# Ejercicio3.net
KiCad netlist of a schematic drawn in Altium Designer
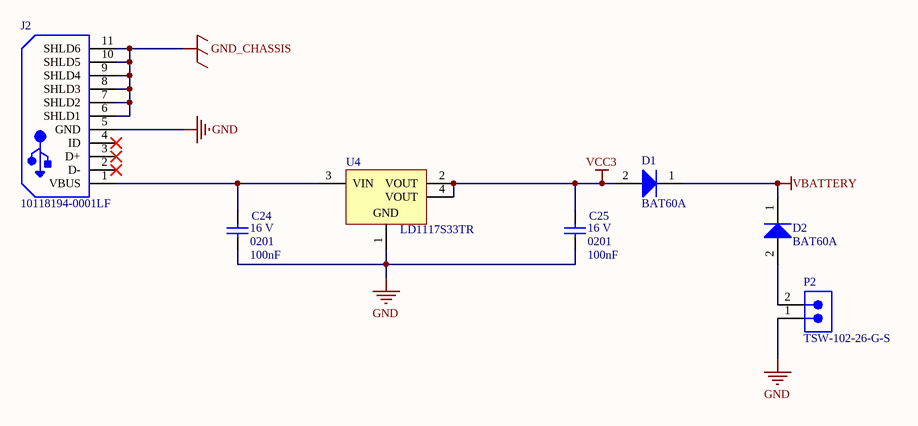
[diagram p0: Ejercicio3.SchDoc]

(export (version "E")
  (design (tool "Eeschema 10.0.6"))
  (components
    (comp (ref "C24")
      (value "100nF")
      (footprint "CAPC0201(0603)33_N")
      (description "CAP 100nF 16V ±10% 0201 (0603 Metric) Thickness 0.33mm SMD")
      (fields
        (field (name "RATED VOLTAGE") "16 V")
        (field (name "TOLERANCE") "Â±10%")
        (field (name "CASE-EIA") "0201")
        (field (name "Comment") "CAP 100nF 16V 0201(0603)")
      )
      (libsource (lib "Altium Content Vault") (part "CMP-1033-00663-1"))
    )
    (comp (ref "C25")
      (value "100nF")
      (footprint "CAPC0201(0603)33_N")
      (description "CAP 100nF 16V ±10% 0201 (0603 Metric) Thickness 0.33mm SMD")
      (fields
        (field (name "RATED VOLTAGE") "16 V")
        (field (name "TOLERANCE") "Â±10%")
        (field (name "CASE-EIA") "0201")
        (field (name "Comment") "CAP 100nF 16V 0201(0603)")
      )
      (libsource (lib "Altium Content Vault") (part "CMP-1033-00663-1"))
    )
    (comp (ref "D1")
      (value "BAT60A")
      (footprint "INF-SOD323_V")
      (description "Silicon Schottky Diode, -55 to 85 degC, SOD323, Reel, Green")
      (fields (field (name "MANUFACTURER") "Infineon"))
      (libsource (lib "Altium Content Vault") (part "INF-D_K1A2-2"))
    )
    (comp (ref "D2")
      (value "BAT60A")
      (footprint "INF-SOD323_V")
      (description "Silicon Schottky Diode, -55 to 85 degC, SOD323, Reel, Green")
      (fields (field (name "MANUFACTURER") "Infineon"))
      (libsource (lib "Altium Content Vault") (part "INF-D_K1A2-2"))
    )
    (comp (ref "J2")
      (value "10118194-0001LF")
      (footprint "FCI-10118194-0001LF-5_V")
      (description "Micro USB B Type Receptacle, 1.8 A, -55 to 85 degC, 5-Pin SMD, RoHS, Tape and Reel")
      (fields (field (name "MANUFACTURER") "Amphenol FCI"))
      (libsource (lib "Altium Content Vault") (part "USB-5-6SHLD"))
    )
    (comp (ref "P2")
      (value "TSW-102-26-G-S")
      (footprint "SMTC-TSW-102-26-XX-S")
      (description "0.025\" SQ Post Header, Through-hole, Vertical, -55 to 125 degC, 2.54 mm Pitch, 2-Pin, Male, RoHS")
      (fields (field (name "MANUFACTURER") "Samtec"))
      (libsource (lib "Altium Content Vault") (part "SMTC-TSW-102-X-X-S-X"))
    )
    (comp (ref "U4")
      (value "LD1117S33TR")
      (footprint "SOT-223_L")
      (description "Fixed Low Drop Positive Voltage Regulator, 3.3V, 4-Pin SOT-223, Tape and Reel")
      (libsource (lib "Altium Content Vault") (part "PM-REG-LD1117-SOT4"))
    )
  )
  (nets
    (net (code "1") (name "GND") (class "Default")
      (node (ref "C24") (pin "2") (pinfunction "2_2") (pintype "passive"))
      (node (ref "C25") (pin "2") (pinfunction "2_2") (pintype "passive"))
      (node (ref "J2") (pin "5") (pinfunction "GND_5") (pintype "passive"))
      (node (ref "P2") (pin "1") (pinfunction "1_1") (pintype "passive"))
      (node (ref "U4") (pin "1") (pinfunction "GND_1") (pintype "power_in"))
    )
    (net (code "2") (name "GND_CHASSIS") (class "Default")
      (node (ref "J2") (pin "10") (pinfunction "SHLD5_10") (pintype "passive"))
      (node (ref "J2") (pin "11") (pinfunction "SHLD6_11") (pintype "passive"))
      (node (ref "J2") (pin "6") (pinfunction "SHLD1_6") (pintype "passive"))
      (node (ref "J2") (pin "7") (pinfunction "SHLD2_7") (pintype "passive"))
      (node (ref "J2") (pin "8") (pinfunction "SHLD3_8") (pintype "passive"))
      (node (ref "J2") (pin "9") (pinfunction "SHLD4_9") (pintype "passive"))
    )
    (net (code "3") (name "Net-(D2-A)") (class "Default")
      (node (ref "D2") (pin "2") (pinfunction "A_2") (pintype "passive"))
      (node (ref "P2") (pin "2") (pinfunction "2_2") (pintype "passive"))
    )
    (net (code "4") (name "Net-(J2-VBUS)") (class "Default")
      (node (ref "C24") (pin "1") (pinfunction "1_1") (pintype "passive"))
      (node (ref "J2") (pin "1") (pinfunction "VBUS_1") (pintype "passive"))
      (node (ref "U4") (pin "3") (pinfunction "VIN_3") (pintype "power_in"))
    )
    (net (code "5") (name "VBATTERY") (class "Default")
      (node (ref "D1") (pin "1") (pinfunction "K_1") (pintype "passive"))
      (node (ref "D2") (pin "1") (pinfunction "K_1") (pintype "passive"))
    )
    (net (code "6") (name "VCC3") (class "Default")
      (node (ref "C25") (pin "1") (pinfunction "1_1") (pintype "passive"))
      (node (ref "D1") (pin "2") (pinfunction "A_2") (pintype "passive"))
      (node (ref "U4") (pin "2") (pinfunction "VOUT_2") (pintype "power_in"))
      (node (ref "U4") (pin "4") (pinfunction "VOUT_4") (pintype "power_in"))
    )
    (net (code "7") (name "unconnected-(J2-D+-Pad3)") (class "Default")
      (node (ref "J2") (pin "3") (pinfunction "D+_3") (pintype "passive+no_connect"))
    )
    (net (code "8") (name "unconnected-(J2-D--Pad2)") (class "Default")
      (node (ref "J2") (pin "2") (pinfunction "D-_2") (pintype "passive+no_connect"))
    )
    (net (code "9") (name "unconnected-(J2-ID-Pad4)") (class "Default")
      (node (ref "J2") (pin "4") (pinfunction "ID_4") (pintype "passive+no_connect"))
    )
  )
)
